# bustracker.net
KiCad netlist of a schematic drawn in EAGLE
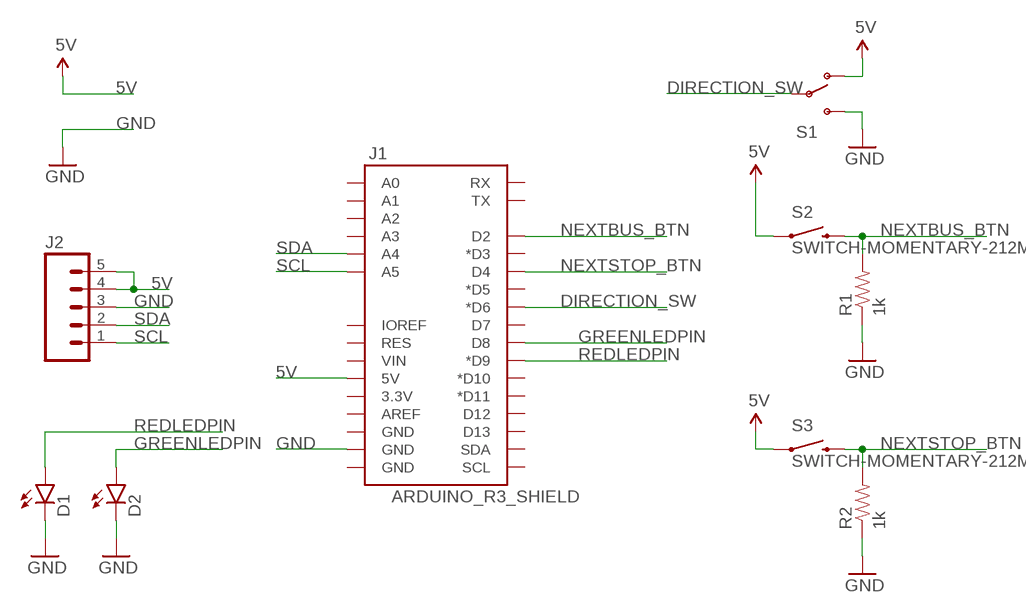
[diagram p0: schematic, sheet 1]

(export (version "E")
  (design (tool "Eeschema 10.0.6"))
  (components
    (comp (ref "D1")
      (value "LED5MM")
      (footprint "eagle-import:LED5MM")
      (libsource (lib "eagle-import") (part "LED5MM"))
    )
    (comp (ref "D2")
      (value "LED5MM")
      (footprint "eagle-import:LED5MM")
      (libsource (lib "eagle-import") (part "LED5MM"))
    )
    (comp (ref "J1")
      (value "ARDUINO_R3_SHIELD")
      (footprint "eagle-import:UNO_R3_SHIELD")
      (libsource (lib "eagle-import") (part "ARDUINO_R3_SHIELD"))
    )
    (comp (ref "J2")
      (value "M05PTH")
      (footprint "eagle-import:1X05")
      (libsource (lib "eagle-import") (part "M05PTH"))
    )
    (comp (ref "R1")
      (value "1k")
      (footprint "eagle-import:AXIAL-0.3")
      (libsource (lib "eagle-import") (part "1KOHM-1/4W-5%(PTH)"))
    )
    (comp (ref "R2")
      (value "1k")
      (footprint "eagle-import:AXIAL-0.3")
      (libsource (lib "eagle-import") (part "1KOHM-1/4W-5%(PTH)"))
    )
    (comp (ref "S1")
      (value "SWITCH-SPDTPTH")
      (footprint "eagle-import:SWITCH-SPDT")
      (libsource (lib "eagle-import") (part "SWITCH-SPDTPTH"))
    )
    (comp (ref "S2")
      (value "SWITCH-MOMENTARY-212MM")
      (footprint "eagle-import:TACTILE-PTH-12MM")
      (libsource (lib "eagle-import") (part "SWITCH-MOMENTARY-212MM"))
    )
    (comp (ref "S3")
      (value "SWITCH-MOMENTARY-212MM")
      (footprint "eagle-import:TACTILE-PTH-12MM")
      (libsource (lib "eagle-import") (part "SWITCH-MOMENTARY-212MM"))
    )
  )
  (nets
    (net (code "1") (name "/DIRECTION_SW") (class "Default")
      (node (ref "J1") (pin "D6") (pinfunction "*D6_D6") (pintype "bidirectional"))
      (node (ref "S1") (pin "2") (pinfunction "P_2") (pintype "passive"))
    )
    (net (code "2") (name "/GREENLEDPIN") (class "Default")
      (node (ref "D2") (pin "A") (pinfunction "A_A") (pintype "passive"))
      (node (ref "J1") (pin "D8") (pinfunction "D8_D8") (pintype "bidirectional"))
    )
    (net (code "3") (name "/NEXTBUS_BTN") (class "Default")
      (node (ref "J1") (pin "D2") (pinfunction "D2_D2") (pintype "bidirectional"))
      (node (ref "R1") (pin "P$2") (pinfunction "2_P$2") (pintype "passive"))
      (node (ref "S2") (pin "3") (pinfunction "2_3") (pintype "passive"))
    )
    (net (code "4") (name "/NEXTSTOP_BTN") (class "Default")
      (node (ref "J1") (pin "D4") (pinfunction "D4_D4") (pintype "bidirectional"))
      (node (ref "R2") (pin "P$2") (pinfunction "2_P$2") (pintype "passive"))
      (node (ref "S3") (pin "3") (pinfunction "2_3") (pintype "passive"))
    )
    (net (code "5") (name "/REDLEDPIN") (class "Default")
      (node (ref "D1") (pin "A") (pinfunction "A_A") (pintype "passive"))
      (node (ref "J1") (pin "D9") (pinfunction "*D9_D9") (pintype "bidirectional"))
    )
    (net (code "6") (name "/SCL") (class "Default")
      (node (ref "J1") (pin "A5") (pinfunction "A5_A5") (pintype "bidirectional"))
      (node (ref "J2") (pin "1") (pinfunction "1_1") (pintype "passive"))
    )
    (net (code "7") (name "/SDA") (class "Default")
      (node (ref "J1") (pin "A4") (pinfunction "A4_A4") (pintype "bidirectional"))
      (node (ref "J2") (pin "2") (pinfunction "2_2") (pintype "passive"))
    )
    (net (code "8") (name "5V") (class "Default")
      (node (ref "J1") (pin "5V") (pinfunction "5V_5V") (pintype "bidirectional"))
      (node (ref "J2") (pin "4") (pinfunction "4_4") (pintype "passive"))
      (node (ref "J2") (pin "5") (pinfunction "5_5") (pintype "passive"))
      (node (ref "S1") (pin "1") (pinfunction "O_1") (pintype "passive"))
      (node (ref "S2") (pin "1") (pinfunction "1_1") (pintype "passive"))
      (node (ref "S3") (pin "1") (pinfunction "1_1") (pintype "passive"))
    )
    (net (code "9") (name "GND") (class "Default")
      (node (ref "D1") (pin "K") (pinfunction "C_K") (pintype "passive"))
      (node (ref "D2") (pin "K") (pinfunction "C_K") (pintype "passive"))
      (node (ref "J1") (pin "GND@1") (pinfunction "GND_GND@1") (pintype "bidirectional"))
      (node (ref "J2") (pin "3") (pinfunction "3_3") (pintype "passive"))
      (node (ref "R1") (pin "P$1") (pinfunction "1_P$1") (pintype "passive"))
      (node (ref "R2") (pin "P$1") (pinfunction "1_P$1") (pintype "passive"))
      (node (ref "S1") (pin "3") (pinfunction "S_3") (pintype "passive"))
    )
    (net (code "10") (name "unconnected-(J1-*D3-PadD3)") (class "Default")
      (node (ref "J1") (pin "D3") (pinfunction "*D3_D3") (pintype "bidirectional"))
    )
    (net (code "11") (name "unconnected-(J1-*D5-PadD5)") (class "Default")
      (node (ref "J1") (pin "D5") (pinfunction "*D5_D5") (pintype "bidirectional"))
    )
    (net (code "12") (name "unconnected-(J1-*D10-PadD10)") (class "Default")
      (node (ref "J1") (pin "D10") (pinfunction "*D10_D10") (pintype "bidirectional"))
    )
    (net (code "13") (name "unconnected-(J1-*D11-PadD11)") (class "Default")
      (node (ref "J1") (pin "D11") (pinfunction "*D11_D11") (pintype "bidirectional"))
    )
    (net (code "14") (name "unconnected-(J1-GND-PadGND@0)") (class "Default")
      (node (ref "J1") (pin "GND@0") (pinfunction "GND_GND@0") (pintype "bidirectional"))
    )
    (net (code "15") (name "unconnected-(J1-GND-PadGND@2)") (class "Default")
      (node (ref "J1") (pin "GND@2") (pinfunction "GND_GND@2") (pintype "bidirectional"))
    )
    (net (code "16") (name "unconnected-(J1-Pad3.3V)") (class "Default")
      (node (ref "J1") (pin "3.3V") (pinfunction "3.3V_3.3V") (pintype "bidirectional"))
    )
    (net (code "17") (name "unconnected-(J1-PadA0)") (class "Default")
      (node (ref "J1") (pin "A0") (pinfunction "A0_A0") (pintype "bidirectional"))
    )
    (net (code "18") (name "unconnected-(J1-PadA1)") (class "Default")
      (node (ref "J1") (pin "A1") (pinfunction "A1_A1") (pintype "bidirectional"))
    )
    (net (code "19") (name "unconnected-(J1-PadA2)") (class "Default")
      (node (ref "J1") (pin "A2") (pinfunction "A2_A2") (pintype "bidirectional"))
    )
    (net (code "20") (name "unconnected-(J1-PadA3)") (class "Default")
      (node (ref "J1") (pin "A3") (pinfunction "A3_A3") (pintype "bidirectional"))
    )
    (net (code "21") (name "unconnected-(J1-PadAREF)") (class "Default")
      (node (ref "J1") (pin "AREF") (pinfunction "AREF_AREF") (pintype "bidirectional"))
    )
    (net (code "22") (name "unconnected-(J1-PadD7)") (class "Default")
      (node (ref "J1") (pin "D7") (pinfunction "D7_D7") (pintype "bidirectional"))
    )
    (net (code "23") (name "unconnected-(J1-PadD12)") (class "Default")
      (node (ref "J1") (pin "D12") (pinfunction "D12_D12") (pintype "bidirectional"))
    )
    (net (code "24") (name "unconnected-(J1-PadD13)") (class "Default")
      (node (ref "J1") (pin "D13") (pinfunction "D13_D13") (pintype "bidirectional"))
    )
    (net (code "25") (name "unconnected-(J1-PadIOREF)") (class "Default")
      (node (ref "J1") (pin "IOREF") (pinfunction "IOREF_IOREF") (pintype "bidirectional"))
    )
    (net (code "26") (name "unconnected-(J1-PadRES)") (class "Default")
      (node (ref "J1") (pin "RES") (pinfunction "RES_RES") (pintype "bidirectional"))
    )
    (net (code "27") (name "unconnected-(J1-PadRX)") (class "Default")
      (node (ref "J1") (pin "RX") (pinfunction "RX_RX") (pintype "bidirectional"))
    )
    (net (code "28") (name "unconnected-(J1-PadSCL)") (class "Default")
      (node (ref "J1") (pin "SCL") (pinfunction "SCL_SCL") (pintype "bidirectional"))
    )
    (net (code "29") (name "unconnected-(J1-PadSDA)") (class "Default")
      (node (ref "J1") (pin "SDA") (pinfunction "SDA_SDA") (pintype "bidirectional"))
    )
    (net (code "30") (name "unconnected-(J1-PadTX)") (class "Default")
      (node (ref "J1") (pin "TX") (pinfunction "TX_TX") (pintype "bidirectional"))
    )
    (net (code "31") (name "unconnected-(J1-PadVIN)") (class "Default")
      (node (ref "J1") (pin "VIN") (pinfunction "VIN_VIN") (pintype "bidirectional"))
    )
  )
)
